# temp_draft.net
KiCad netlist of a schematic drawn in EAGLE
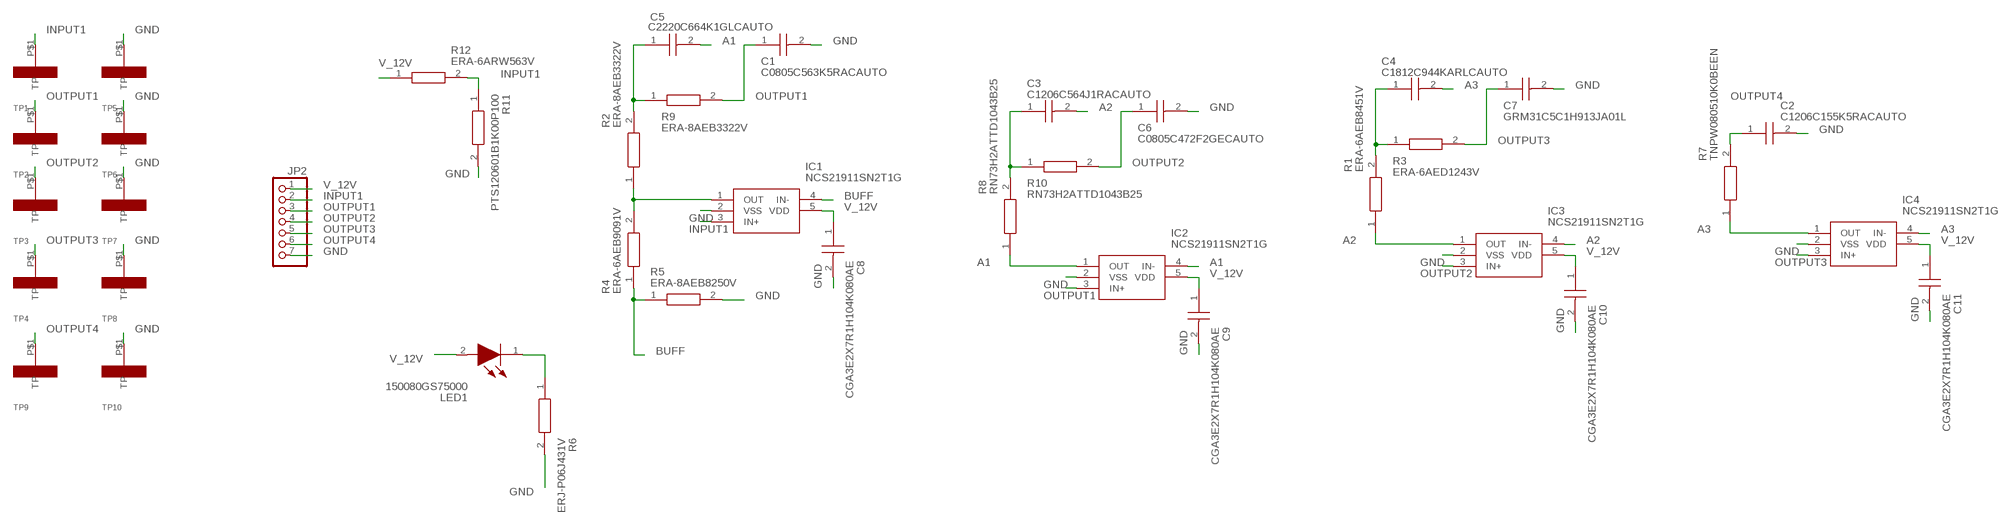
[diagram p0: schematic, sheet 1]

(export (version "E")
  (design (tool "Eeschema 10.0.6"))
  (components
    (comp (ref "C1")
      (value "C0805C563K5RACAUTO")
      (footprint "eagle-import:CAPC0805C563K")
      (fields (field (name "MOUSER_PART_NUMBER") "80-C0805C563K5RAUTO"))
      (libsource (lib "eagle-import") (part "C0805C563K5RACAUTO"))
    )
    (comp (ref "C2")
      (value "C1206C155K5RACAUTO")
      (footprint "eagle-import:CAPC1206C")
      (fields (field (name "MOUSER_PART_NUMBER") "80-C1206C155K5RAUTO"))
      (libsource (lib "eagle-import") (part "C1206C155K5RACAUTO"))
    )
    (comp (ref "C3")
      (value "C1206C564J1RACAUTO")
      (footprint "eagle-import:CAPC1206")
      (fields (field (name "MOUSER_PART_NUMBER") "80-C1206C564J1RAUTO"))
      (libsource (lib "eagle-import") (part "C1206C564J1RACAUTO"))
    )
    (comp (ref "C4")
      (value "C1812C944KARLCAUTO")
      (footprint "eagle-import:CAPC4532X380N")
      (fields (field (name "MOUSER_PART_NUMBER") "80-C1812C944KARLAUTO"))
      (libsource (lib "eagle-import") (part "C1812C944KARLCAUTO"))
    )
    (comp (ref "C5")
      (value "C2220C664K1GLCAUTO")
      (footprint "eagle-import:CAPC2220")
      (fields (field (name "MOUSER_PART_NUMBER") "80-C2220C664K1GLAUTO"))
      (libsource (lib "eagle-import") (part "C2220C664K1GLCAUTO"))
    )
    (comp (ref "C6")
      (value "C0805C472F2GECAUTO")
      (footprint "eagle-import:CAPC2012X100N")
      (fields (field (name "MOUSER_PART_NUMBER") "80-C0805C472F2GECAUT"))
      (libsource (lib "eagle-import") (part "C0805C472F2GECAUTO"))
    )
    (comp (ref "C7")
      (value "GRM31C5C1H913JA01L")
      (footprint "eagle-import:CAPC3216X180N")
      (libsource (lib "eagle-import") (part "GRM31C5C1H913JA01L"))
    )
    (comp (ref "C8")
      (value "CGA3E2X7R1H104K080AE")
      (footprint "eagle-import:CAPC1608X90N")
      (fields (field (name "MOUSER_PART_NUMBER") "810-CGA3E2X7R1H104KE"))
      (libsource (lib "eagle-import") (part "CGA3E2X7R1H104K080AE"))
    )
    (comp (ref "C9")
      (value "CGA3E2X7R1H104K080AE")
      (footprint "eagle-import:CAPC1608X90N")
      (fields (field (name "MOUSER_PART_NUMBER") "810-CGA3E2X7R1H104KE"))
      (libsource (lib "eagle-import") (part "CGA3E2X7R1H104K080AE"))
    )
    (comp (ref "C10")
      (value "CGA3E2X7R1H104K080AE")
      (footprint "eagle-import:CAPC1608X90N")
      (fields (field (name "MOUSER_PART_NUMBER") "810-CGA3E2X7R1H104KE"))
      (libsource (lib "eagle-import") (part "CGA3E2X7R1H104K080AE"))
    )
    (comp (ref "C11")
      (value "CGA3E2X7R1H104K080AE")
      (footprint "eagle-import:CAPC1608X90N")
      (fields (field (name "MOUSER_PART_NUMBER") "810-CGA3E2X7R1H104KE"))
      (libsource (lib "eagle-import") (part "CGA3E2X7R1H104K080AE"))
    )
    (comp (ref "IC1")
      (value "NCS21911SN2T1G")
      (footprint "eagle-import:SOT95P275X110-5N")
      (fields (field (name "MOUSER_PART_NUMBER") "863-NCS21911SN2T1G"))
      (libsource (lib "eagle-import") (part "NCS21911SN2T1G"))
    )
    (comp (ref "IC2")
      (value "NCS21911SN2T1G")
      (footprint "eagle-import:SOT95P275X110-5N")
      (fields (field (name "MOUSER_PART_NUMBER") "863-NCS21911SN2T1G"))
      (libsource (lib "eagle-import") (part "NCS21911SN2T1G"))
    )
    (comp (ref "IC3")
      (value "NCS21911SN2T1G")
      (footprint "eagle-import:SOT95P275X110-5N")
      (fields (field (name "MOUSER_PART_NUMBER") "863-NCS21911SN2T1G"))
      (libsource (lib "eagle-import") (part "NCS21911SN2T1G"))
    )
    (comp (ref "IC4")
      (value "NCS21911SN2T1G")
      (footprint "eagle-import:SOT95P275X110-5N")
      (fields (field (name "MOUSER_PART_NUMBER") "863-NCS21911SN2T1G"))
      (libsource (lib "eagle-import") (part "NCS21911SN2T1G"))
    )
    (comp (ref "JP2")
      (value "PINHD-1X7")
      (footprint "eagle-import:1X07")
      (libsource (lib "eagle-import") (part "PINHD-1X7"))
    )
    (comp (ref "LED1")
      (value "150080GS75000")
      (footprint "eagle-import:LEDM2012X80N")
      (fields (field (name "MOUSER_PART_NUMBER") "710-150080GS75000"))
      (libsource (lib "eagle-import") (part "150080GS75000"))
    )
    (comp (ref "R1")
      (value "ERA-6AEB8451V")
      (footprint "eagle-import:ERA6A_(0805)")
      (fields (field (name "MOUSER_PART_NUMBER") "667-ERA-6AEB8451V"))
      (libsource (lib "eagle-import") (part "ERA-6AEB8451V"))
    )
    (comp (ref "R2")
      (value "ERA-8AEB3322V")
      (footprint "eagle-import:ERA8A_(0805)")
      (fields (field (name "MOUSER_PART_NUMBER") "667-ERA-8AEB3322V"))
      (libsource (lib "eagle-import") (part "ERA-8AEB3322V"))
    )
    (comp (ref "R3")
      (value "ERA-6AED1243V")
      (footprint "eagle-import:ERA6A_(0805)")
      (libsource (lib "eagle-import") (part "ERA-6AED1243V"))
    )
    (comp (ref "R4")
      (value "ERA-6AEB9091V")
      (footprint "eagle-import:ERA6A_(0805)")
      (fields (field (name "MOUSER_PART_NUMBER") "667-ERA-6AEB9091V"))
      (libsource (lib "eagle-import") (part "ERA-6AEB9091V"))
    )
    (comp (ref "R5")
      (value "ERA-8AEB8250V")
      (footprint "eagle-import:ERA8A_(0805)")
      (libsource (lib "eagle-import") (part "ERA-8AEB8250V"))
    )
    (comp (ref "R6")
      (value "ERJ-P06J431V")
      (footprint "eagle-import:ERJP06_(0805)")
      (fields (field (name "MOUSER_PART_NUMBER") "667-ERJ-P06J431V"))
      (libsource (lib "eagle-import") (part "ERJ-P06J431V"))
    )
    (comp (ref "R7")
      (value "TNPW080510K0BEEN")
      (footprint "eagle-import:RESC2013X65N")
      (fields (field (name "MOUSER_PART_NUMBER") "71-TNPW080510K0BEEN"))
      (libsource (lib "eagle-import") (part "TNPW080510K0BEEN"))
    )
    (comp (ref "R8")
      (value "RN73H2ATTD1043B25")
      (footprint "eagle-import:ERA6A_(0805)")
      (fields (field (name "MOUSER_PART_NUMBER") "660-RN73H2ATD1043B25"))
      (libsource (lib "eagle-import") (part "RN73H2ATTD1043B25"))
    )
    (comp (ref "R9")
      (value "ERA-8AEB3322V")
      (footprint "eagle-import:ERA8A_(0805)")
      (fields (field (name "MOUSER_PART_NUMBER") "667-ERA-8AEB3322V"))
      (libsource (lib "eagle-import") (part "ERA-8AEB3322V"))
    )
    (comp (ref "R10")
      (value "RN73H2ATTD1043B25")
      (footprint "eagle-import:ERA6A_(0805)")
      (fields (field (name "MOUSER_PART_NUMBER") "660-RN73H2ATD1043B25"))
      (libsource (lib "eagle-import") (part "RN73H2ATTD1043B25"))
    )
    (comp (ref "R11")
      (value "PTS120601B1K00P100")
      (footprint "eagle-import:PTS1206")
      (fields (field (name "MOUSER_PART_NUMBER") "594-PTS120601B1K00P"))
      (libsource (lib "eagle-import") (part "PTS120601B1K00P100"))
    )
    (comp (ref "R12")
      (value "ERA-6ARW563V")
      (footprint "eagle-import:ERA6A_(0805)")
      (libsource (lib "eagle-import") (part "ERA-6ARW563V"))
    )
    (comp (ref "TP1")
      (value "S1751-46R")
      (footprint "eagle-import:1.85X3.45_MM")
      (libsource (lib "eagle-import") (part "S1751-46R"))
    )
    (comp (ref "TP2")
      (value "S1751-46R")
      (footprint "eagle-import:1.85X3.45_MM")
      (libsource (lib "eagle-import") (part "S1751-46R"))
    )
    (comp (ref "TP3")
      (value "S1751-46R")
      (footprint "eagle-import:1.85X3.45_MM")
      (libsource (lib "eagle-import") (part "S1751-46R"))
    )
    (comp (ref "TP4")
      (value "S1751-46R")
      (footprint "eagle-import:1.85X3.45_MM")
      (libsource (lib "eagle-import") (part "S1751-46R"))
    )
    (comp (ref "TP5")
      (value "S1751-46R")
      (footprint "eagle-import:1.85X3.45_MM")
      (libsource (lib "eagle-import") (part "S1751-46R"))
    )
    (comp (ref "TP6")
      (value "S1751-46R")
      (footprint "eagle-import:1.85X3.45_MM")
      (libsource (lib "eagle-import") (part "S1751-46R"))
    )
    (comp (ref "TP7")
      (value "S1751-46R")
      (footprint "eagle-import:1.85X3.45_MM")
      (libsource (lib "eagle-import") (part "S1751-46R"))
    )
    (comp (ref "TP8")
      (value "S1751-46R")
      (footprint "eagle-import:1.85X3.45_MM")
      (libsource (lib "eagle-import") (part "S1751-46R"))
    )
    (comp (ref "TP9")
      (value "S1751-46R")
      (footprint "eagle-import:1.85X3.45_MM")
      (libsource (lib "eagle-import") (part "S1751-46R"))
    )
    (comp (ref "TP10")
      (value "S1751-46R")
      (footprint "eagle-import:1.85X3.45_MM")
      (libsource (lib "eagle-import") (part "S1751-46R"))
    )
  )
  (nets
    (net (code "1") (name "/A1") (class "Default")
      (node (ref "C5") (pin "2") (pinfunction "2_2") (pintype "bidirectional"))
      (node (ref "IC2") (pin "1") (pinfunction "OUT_1") (pintype "bidirectional"))
      (node (ref "IC2") (pin "4") (pinfunction "IN-_4") (pintype "bidirectional"))
      (node (ref "R8") (pin "1") (pinfunction "1_1") (pintype "bidirectional"))
    )
    (net (code "2") (name "/A2") (class "Default")
      (node (ref "C3") (pin "2") (pinfunction "2_2") (pintype "bidirectional"))
      (node (ref "IC3") (pin "1") (pinfunction "OUT_1") (pintype "bidirectional"))
      (node (ref "IC3") (pin "4") (pinfunction "IN-_4") (pintype "bidirectional"))
      (node (ref "R1") (pin "1") (pinfunction "1_1") (pintype "bidirectional"))
    )
    (net (code "3") (name "/A3") (class "Default")
      (node (ref "C4") (pin "2") (pinfunction "2_2") (pintype "bidirectional"))
      (node (ref "IC4") (pin "1") (pinfunction "OUT_1") (pintype "bidirectional"))
      (node (ref "IC4") (pin "4") (pinfunction "IN-_4") (pintype "bidirectional"))
      (node (ref "R7") (pin "1") (pinfunction "1_1") (pintype "bidirectional"))
    )
    (net (code "4") (name "/BUFF") (class "Default")
      (node (ref "IC1") (pin "4") (pinfunction "IN-_4") (pintype "bidirectional"))
      (node (ref "R4") (pin "1") (pinfunction "1_1") (pintype "bidirectional"))
      (node (ref "R5") (pin "1") (pinfunction "1_1") (pintype "bidirectional"))
    )
    (net (code "5") (name "/GND") (class "Default")
      (node (ref "C1") (pin "2") (pinfunction "2_2") (pintype "bidirectional"))
      (node (ref "C10") (pin "2") (pinfunction "2_2") (pintype "bidirectional"))
      (node (ref "C11") (pin "2") (pinfunction "2_2") (pintype "bidirectional"))
      (node (ref "C2") (pin "2") (pinfunction "2_2") (pintype "bidirectional"))
      (node (ref "C6") (pin "2") (pinfunction "2_2") (pintype "bidirectional"))
      (node (ref "C7") (pin "2") (pinfunction "2_2") (pintype "bidirectional"))
      (node (ref "C8") (pin "2") (pinfunction "2_2") (pintype "bidirectional"))
      (node (ref "C9") (pin "2") (pinfunction "2_2") (pintype "bidirectional"))
      (node (ref "IC1") (pin "2") (pinfunction "VSS_2") (pintype "bidirectional"))
      (node (ref "IC2") (pin "2") (pinfunction "VSS_2") (pintype "bidirectional"))
      (node (ref "IC3") (pin "2") (pinfunction "VSS_2") (pintype "bidirectional"))
      (node (ref "IC4") (pin "2") (pinfunction "VSS_2") (pintype "bidirectional"))
      (node (ref "JP2") (pin "7") (pinfunction "7_7") (pintype "passive"))
      (node (ref "R11") (pin "2") (pinfunction "2_2") (pintype "bidirectional"))
      (node (ref "R5") (pin "2") (pinfunction "2_2") (pintype "bidirectional"))
      (node (ref "R6") (pin "2") (pinfunction "2_2") (pintype "bidirectional"))
      (node (ref "TP10") (pin "P$1") (pinfunction "TP_P$1") (pintype "bidirectional"))
      (node (ref "TP5") (pin "P$1") (pinfunction "TP_P$1") (pintype "bidirectional"))
      (node (ref "TP6") (pin "P$1") (pinfunction "TP_P$1") (pintype "bidirectional"))
      (node (ref "TP7") (pin "P$1") (pinfunction "TP_P$1") (pintype "bidirectional"))
      (node (ref "TP8") (pin "P$1") (pinfunction "TP_P$1") (pintype "bidirectional"))
    )
    (net (code "6") (name "/INPUT1") (class "Default")
      (node (ref "IC1") (pin "3") (pinfunction "IN+_3") (pintype "bidirectional"))
      (node (ref "JP2") (pin "2") (pinfunction "2_2") (pintype "passive"))
      (node (ref "R11") (pin "1") (pinfunction "1_1") (pintype "bidirectional"))
      (node (ref "R12") (pin "2") (pinfunction "2_2") (pintype "bidirectional"))
      (node (ref "TP1") (pin "P$1") (pinfunction "TP_P$1") (pintype "bidirectional"))
    )
    (net (code "7") (name "/OUTPUT1") (class "Default")
      (node (ref "C1") (pin "1") (pinfunction "1_1") (pintype "bidirectional"))
      (node (ref "IC2") (pin "3") (pinfunction "IN+_3") (pintype "bidirectional"))
      (node (ref "JP2") (pin "3") (pinfunction "3_3") (pintype "passive"))
      (node (ref "R9") (pin "2") (pinfunction "2_2") (pintype "bidirectional"))
      (node (ref "TP2") (pin "P$1") (pinfunction "TP_P$1") (pintype "bidirectional"))
    )
    (net (code "8") (name "/OUTPUT2") (class "Default")
      (node (ref "C6") (pin "1") (pinfunction "1_1") (pintype "bidirectional"))
      (node (ref "IC3") (pin "3") (pinfunction "IN+_3") (pintype "bidirectional"))
      (node (ref "JP2") (pin "4") (pinfunction "4_4") (pintype "passive"))
      (node (ref "R10") (pin "2") (pinfunction "2_2") (pintype "bidirectional"))
      (node (ref "TP3") (pin "P$1") (pinfunction "TP_P$1") (pintype "bidirectional"))
    )
    (net (code "9") (name "/OUTPUT3") (class "Default")
      (node (ref "C7") (pin "1") (pinfunction "1_1") (pintype "bidirectional"))
      (node (ref "IC4") (pin "3") (pinfunction "IN+_3") (pintype "bidirectional"))
      (node (ref "JP2") (pin "5") (pinfunction "5_5") (pintype "passive"))
      (node (ref "R3") (pin "2") (pinfunction "2_2") (pintype "bidirectional"))
      (node (ref "TP4") (pin "P$1") (pinfunction "TP_P$1") (pintype "bidirectional"))
    )
    (net (code "10") (name "/OUTPUT4") (class "Default")
      (node (ref "C2") (pin "1") (pinfunction "1_1") (pintype "bidirectional"))
      (node (ref "JP2") (pin "6") (pinfunction "6_6") (pintype "passive"))
      (node (ref "R7") (pin "2") (pinfunction "2_2") (pintype "bidirectional"))
      (node (ref "TP9") (pin "P$1") (pinfunction "TP_P$1") (pintype "bidirectional"))
    )
    (net (code "11") (name "/V_12V") (class "Default")
      (node (ref "C10") (pin "1") (pinfunction "1_1") (pintype "bidirectional"))
      (node (ref "C11") (pin "1") (pinfunction "1_1") (pintype "bidirectional"))
      (node (ref "C8") (pin "1") (pinfunction "1_1") (pintype "bidirectional"))
      (node (ref "C9") (pin "1") (pinfunction "1_1") (pintype "bidirectional"))
      (node (ref "IC1") (pin "5") (pinfunction "VDD_5") (pintype "bidirectional"))
      (node (ref "IC2") (pin "5") (pinfunction "VDD_5") (pintype "bidirectional"))
      (node (ref "IC3") (pin "5") (pinfunction "VDD_5") (pintype "bidirectional"))
      (node (ref "IC4") (pin "5") (pinfunction "VDD_5") (pintype "bidirectional"))
      (node (ref "JP2") (pin "1") (pinfunction "1_1") (pintype "passive"))
      (node (ref "LED1") (pin "2") (pinfunction "A_2") (pintype "bidirectional"))
      (node (ref "R12") (pin "1") (pinfunction "1_1") (pintype "bidirectional"))
    )
    (net (code "12") (name "Net-(C3-Pad1)") (class "Default")
      (node (ref "C3") (pin "1") (pinfunction "1_1") (pintype "bidirectional"))
      (node (ref "R10") (pin "1") (pinfunction "1_1") (pintype "bidirectional"))
      (node (ref "R8") (pin "2") (pinfunction "2_2") (pintype "bidirectional"))
    )
    (net (code "13") (name "Net-(C4-Pad1)") (class "Default")
      (node (ref "C4") (pin "1") (pinfunction "1_1") (pintype "bidirectional"))
      (node (ref "R1") (pin "2") (pinfunction "2_2") (pintype "bidirectional"))
      (node (ref "R3") (pin "1") (pinfunction "1_1") (pintype "bidirectional"))
    )
    (net (code "14") (name "Net-(C5-Pad1)") (class "Default")
      (node (ref "C5") (pin "1") (pinfunction "1_1") (pintype "bidirectional"))
      (node (ref "R2") (pin "2") (pinfunction "2_2") (pintype "bidirectional"))
      (node (ref "R9") (pin "1") (pinfunction "1_1") (pintype "bidirectional"))
    )
    (net (code "15") (name "Net-(IC1-OUT)") (class "Default")
      (node (ref "IC1") (pin "1") (pinfunction "OUT_1") (pintype "bidirectional"))
      (node (ref "R2") (pin "1") (pinfunction "1_1") (pintype "bidirectional"))
      (node (ref "R4") (pin "2") (pinfunction "2_2") (pintype "bidirectional"))
    )
    (net (code "16") (name "Net-(LED1-K)") (class "Default")
      (node (ref "LED1") (pin "1") (pinfunction "K_1") (pintype "bidirectional"))
      (node (ref "R6") (pin "1") (pinfunction "1_1") (pintype "bidirectional"))
    )
  )
)
